# obc-v2_CM4-SPI-UART.net
KiCad netlist of a schematic drawn in Altium Designer
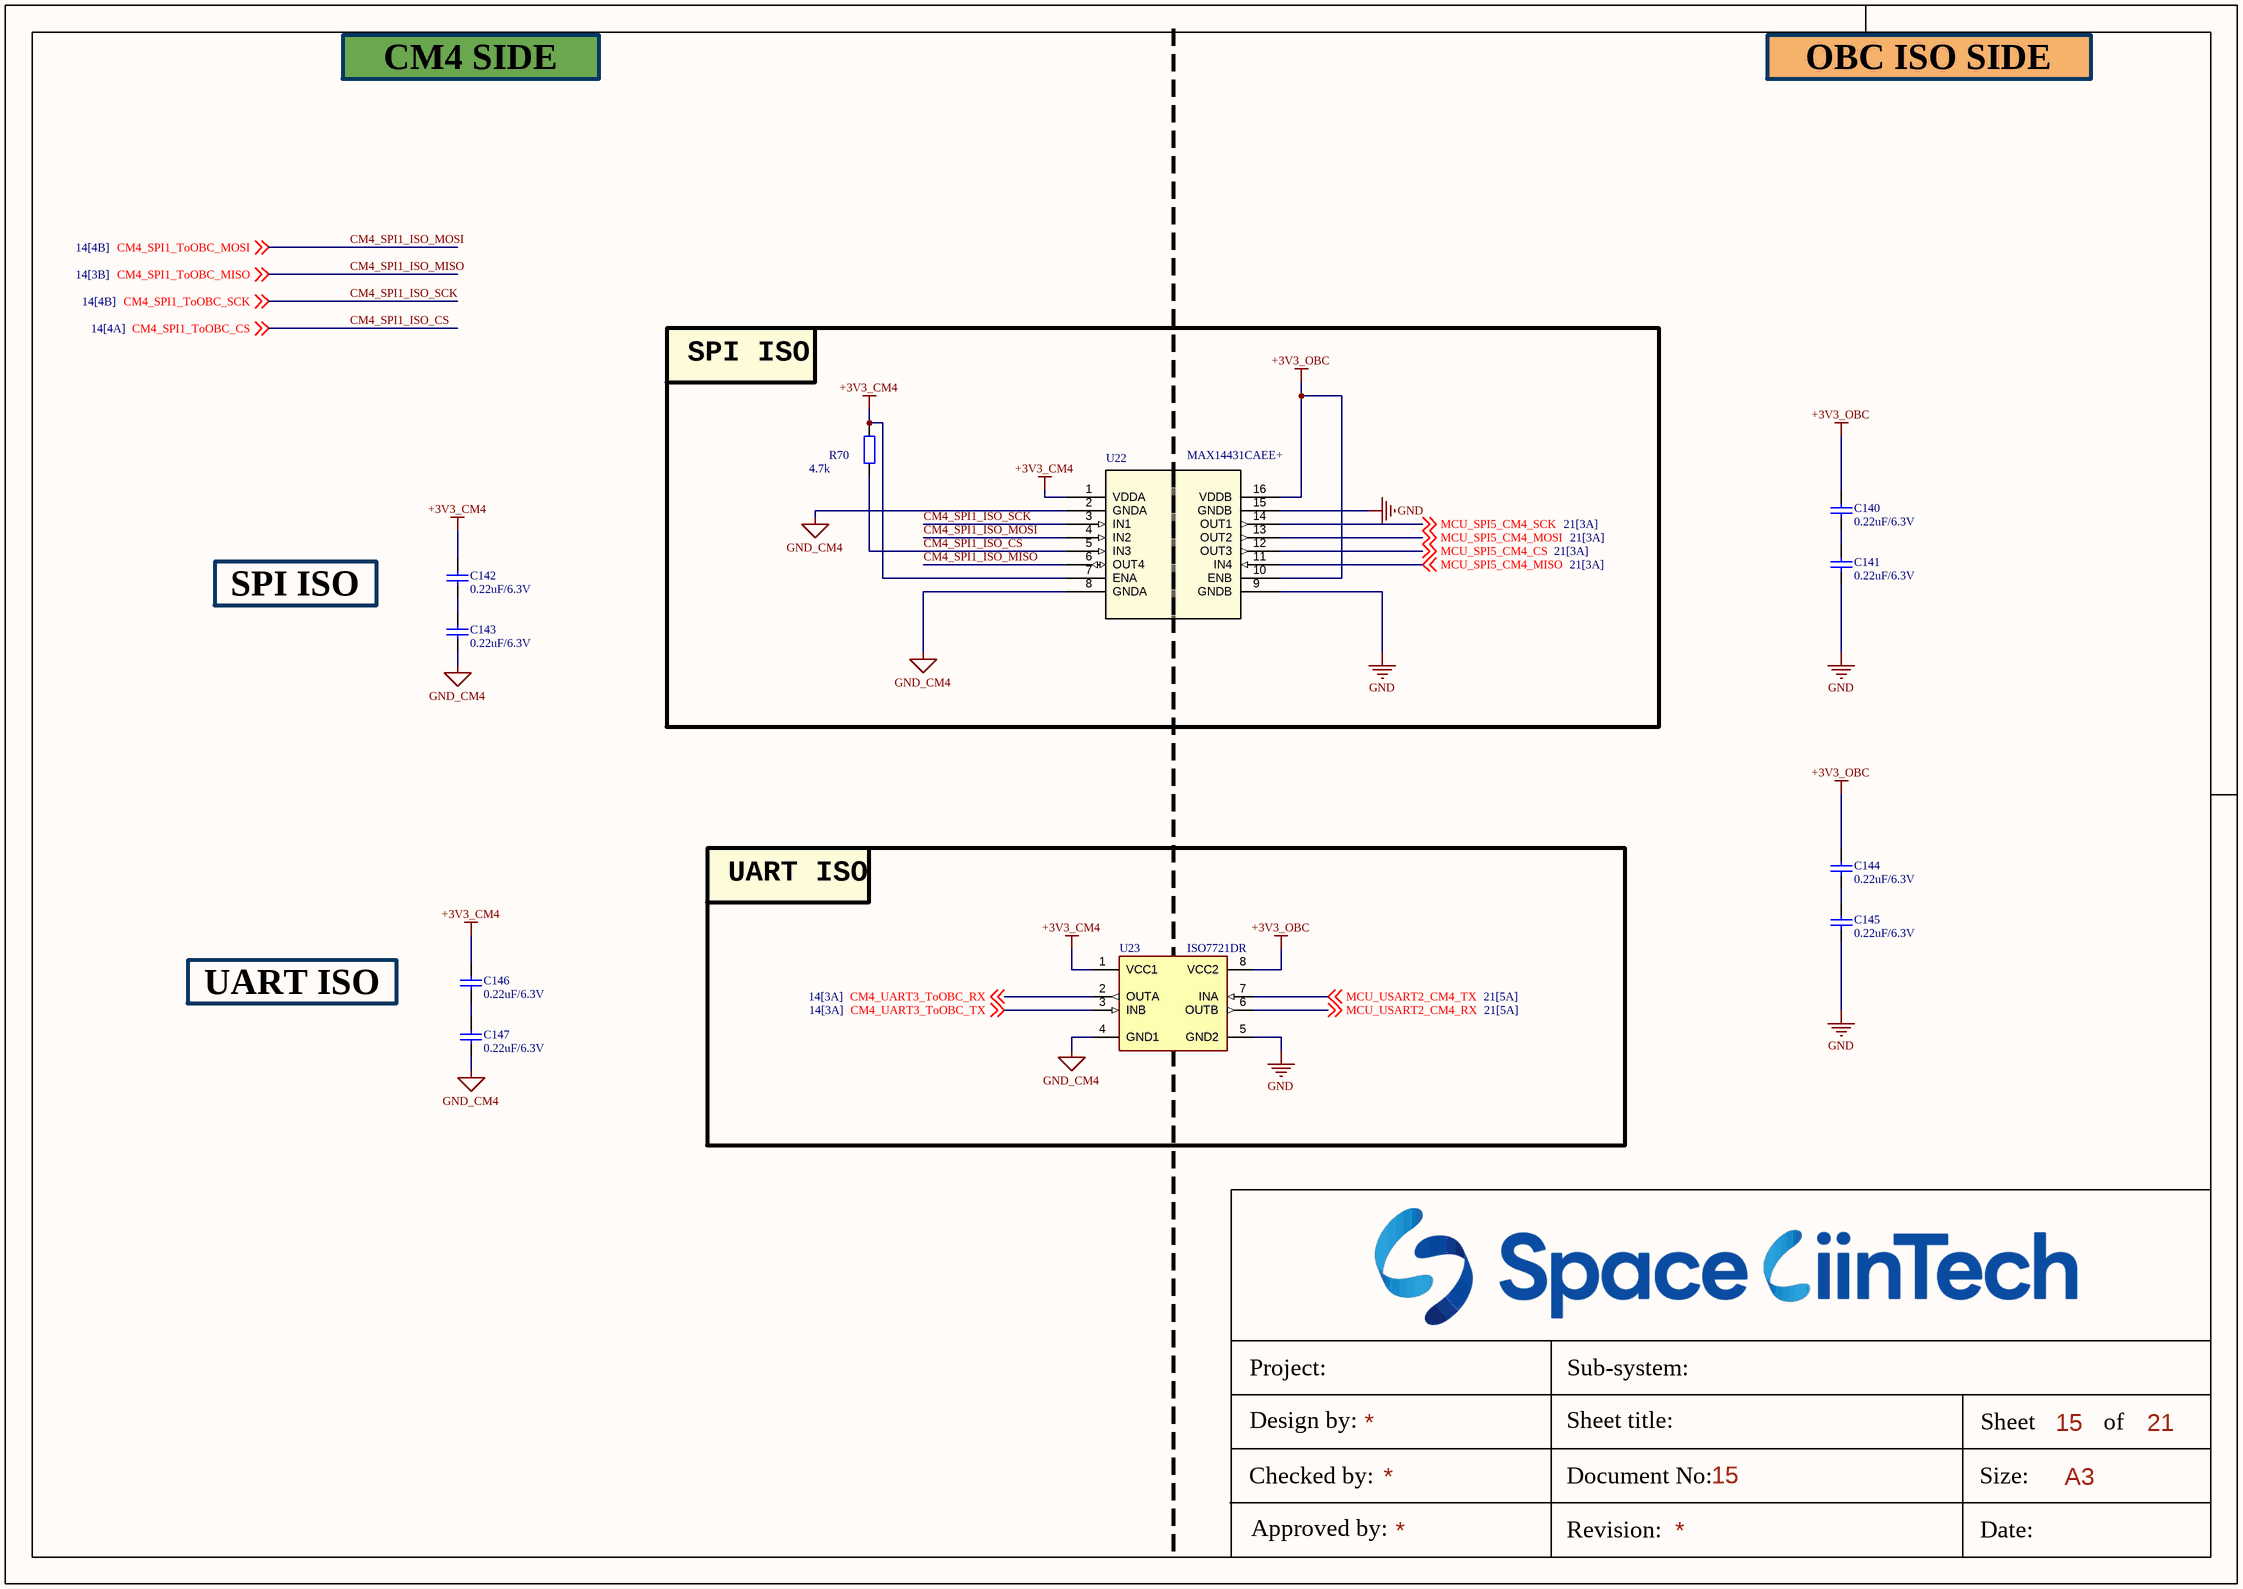
[diagram p0: obc-v2_CM4-SPI-UART.SchDoc]

(export (version "E")
  (design (tool "Eeschema 10.0.6"))
  (components
    (comp (ref "C140")
      (value "0.22uF/6.3V")
      (footprint "CAP_C_1005X60")
      (description "CAPC")
      (libsource (lib "Altium_Lib_by_KhueNguyenCreator") (part "Tu 0402 33nF 10V"))
    )
    (comp (ref "C141")
      (value "0.22uF/6.3V")
      (footprint "CAP_C_1005X60")
      (description "CAPC")
      (libsource (lib "Altium_Lib_by_KhueNguyenCreator") (part "Tu 0402 33nF 10V"))
    )
    (comp (ref "C142")
      (value "0.22uF/6.3V")
      (footprint "CAP_C_1005X60")
      (description "CAPC")
      (libsource (lib "Altium_Lib_by_KhueNguyenCreator") (part "Tu 0402 33nF 10V"))
    )
    (comp (ref "C143")
      (value "0.22uF/6.3V")
      (footprint "CAP_C_1005X60")
      (description "CAPC")
      (libsource (lib "Altium_Lib_by_KhueNguyenCreator") (part "Tu 0402 33nF 10V"))
    )
    (comp (ref "C144")
      (value "0.22uF/6.3V")
      (footprint "CAP_C_1005X60")
      (description "CAPC")
      (libsource (lib "Altium_Lib_by_KhueNguyenCreator") (part "Tu 0402 33nF 10V"))
    )
    (comp (ref "C145")
      (value "0.22uF/6.3V")
      (footprint "CAP_C_1005X60")
      (description "CAPC")
      (libsource (lib "Altium_Lib_by_KhueNguyenCreator") (part "Tu 0402 33nF 10V"))
    )
    (comp (ref "C146")
      (value "0.22uF/6.3V")
      (footprint "CAP_C_1005X60")
      (description "CAPC")
      (libsource (lib "Altium_Lib_by_KhueNguyenCreator") (part "Tu 0402 33nF 10V"))
    )
    (comp (ref "C147")
      (value "0.22uF/6.3V")
      (footprint "CAP_C_1005X60")
      (description "CAPC")
      (libsource (lib "Altium_Lib_by_KhueNguyenCreator") (part "Tu 0402 33nF 10V"))
    )
    (comp (ref "R70")
      (value "4.7k")
      (footprint "RES_C_1608X60")
      (description "RES")
      (libsource (lib "Altium_Lib_by_KhueNguyenCreator") (part "Tro 0603 1% 10k"))
    )
    (comp (ref "U22")
      (value "MAX14431CAEE+")
      (footprint "21-0055Q_E16MS+1F_MXM")
      (description "No Description Available")
      (libsource (lib "MAX14431CAEE&plus_") (part "MAX14431CAEE+"))
    )
    (comp (ref "U23")
      (value "ISO7721DR")
      (footprint "SOIC127P602X173-8N")
      (description "Robust EMC, dual-channel, 1/1, reinforced digital isolator 8-SOIC -55 to 125")
      (libsource (lib "ISO7721DR") (part "ISO7721DR"))
    )
  )
  (nets
    (net (code "1") (name "+3V3_CM4") (class "Default")
      (node (ref "C142") (pin "1") (pinfunction "1_1") (pintype "passive"))
      (node (ref "C146") (pin "1") (pinfunction "1_1") (pintype "passive"))
      (node (ref "R70") (pin "2") (pinfunction "2_2") (pintype "passive"))
      (node (ref "U22") (pin "1") (pinfunction "VDDA_1") (pintype "power_in"))
      (node (ref "U22") (pin "7") (pinfunction "ENA_7") (pintype "passive"))
      (node (ref "U23") (pin "1") (pinfunction "VCC1_1") (pintype "power_in"))
    )
    (net (code "2") (name "+3V3_OBC") (class "Default")
      (node (ref "C140") (pin "2") (pinfunction "2_2") (pintype "passive"))
      (node (ref "C144") (pin "2") (pinfunction "2_2") (pintype "passive"))
      (node (ref "U22") (pin "10") (pinfunction "ENB_10") (pintype "passive"))
      (node (ref "U22") (pin "16") (pinfunction "VDDB_16") (pintype "power_in"))
      (node (ref "U23") (pin "8") (pinfunction "VCC2_8") (pintype "power_in"))
    )
    (net (code "3") (name "CM4_SPI1_ToOBC_CS") (class "Default")
      (node (ref "R70") (pin "1") (pinfunction "1_1") (pintype "passive"))
      (node (ref "U22") (pin "5") (pinfunction "IN3_5") (pintype "input"))
    )
    (net (code "4") (name "CM4_SPI1_ToOBC_MISO") (class "Default")
      (node (ref "U22") (pin "6") (pinfunction "OUT4_6") (pintype "bidirectional"))
    )
    (net (code "5") (name "CM4_SPI1_ToOBC_MOSI") (class "Default")
      (node (ref "U22") (pin "4") (pinfunction "IN2_4") (pintype "input"))
    )
    (net (code "6") (name "CM4_SPI1_ToOBC_SCK") (class "Default")
      (node (ref "U22") (pin "3") (pinfunction "IN1_3") (pintype "input"))
    )
    (net (code "7") (name "CM4_UART3_ToOBC_RX") (class "Default")
      (node (ref "U23") (pin "2") (pinfunction "OUTA_2") (pintype "output"))
    )
    (net (code "8") (name "CM4_UART3_ToOBC_TX") (class "Default")
      (node (ref "U23") (pin "3") (pinfunction "INB_3") (pintype "input"))
    )
    (net (code "9") (name "GND") (class "Default")
      (node (ref "C141") (pin "1") (pinfunction "1_1") (pintype "passive"))
      (node (ref "C145") (pin "1") (pinfunction "1_1") (pintype "passive"))
      (node (ref "U22") (pin "15") (pinfunction "GNDB_15") (pintype "power_in"))
      (node (ref "U22") (pin "9") (pinfunction "GNDB_9") (pintype "power_in"))
      (node (ref "U23") (pin "5") (pinfunction "GND2_5") (pintype "power_in"))
    )
    (net (code "10") (name "GND_CM4") (class "Default")
      (node (ref "C143") (pin "2") (pinfunction "2_2") (pintype "passive"))
      (node (ref "C147") (pin "2") (pinfunction "2_2") (pintype "passive"))
      (node (ref "U22") (pin "2") (pinfunction "GNDA_2") (pintype "power_in"))
      (node (ref "U22") (pin "8") (pinfunction "GNDA_8") (pintype "power_in"))
      (node (ref "U23") (pin "4") (pinfunction "GND1_4") (pintype "power_in"))
    )
    (net (code "11") (name "MCU_SPI5_CM4_CS") (class "Default")
      (node (ref "U22") (pin "12") (pinfunction "OUT3_12") (pintype "output"))
    )
    (net (code "12") (name "MCU_SPI5_CM4_MISO") (class "Default")
      (node (ref "U22") (pin "11") (pinfunction "IN4_11") (pintype "input"))
    )
    (net (code "13") (name "MCU_SPI5_CM4_MOSI") (class "Default")
      (node (ref "U22") (pin "13") (pinfunction "OUT2_13") (pintype "output"))
    )
    (net (code "14") (name "MCU_SPI5_CM4_SCK") (class "Default")
      (node (ref "U22") (pin "14") (pinfunction "OUT1_14") (pintype "output"))
    )
    (net (code "15") (name "MCU_USART2_CM4_RX") (class "Default")
      (node (ref "U23") (pin "6") (pinfunction "OUTB_6") (pintype "output"))
    )
    (net (code "16") (name "MCU_USART2_CM4_TX") (class "Default")
      (node (ref "U23") (pin "7") (pinfunction "INA_7") (pintype "input"))
    )
    (net (code "17") (name "Net-(C140-Pad1)") (class "Default")
      (node (ref "C140") (pin "1") (pinfunction "1_1") (pintype "passive"))
      (node (ref "C141") (pin "2") (pinfunction "2_2") (pintype "passive"))
    )
    (net (code "18") (name "Net-(C142-Pad2)") (class "Default")
      (node (ref "C142") (pin "2") (pinfunction "2_2") (pintype "passive"))
      (node (ref "C143") (pin "1") (pinfunction "1_1") (pintype "passive"))
    )
    (net (code "19") (name "Net-(C144-Pad1)") (class "Default")
      (node (ref "C144") (pin "1") (pinfunction "1_1") (pintype "passive"))
      (node (ref "C145") (pin "2") (pinfunction "2_2") (pintype "passive"))
    )
    (net (code "20") (name "Net-(C146-Pad2)") (class "Default")
      (node (ref "C146") (pin "2") (pinfunction "2_2") (pintype "passive"))
      (node (ref "C147") (pin "1") (pinfunction "1_1") (pintype "passive"))
    )
  )
)
